# promini_3.net
KiCad netlist of a schematic drawn in EAGLE
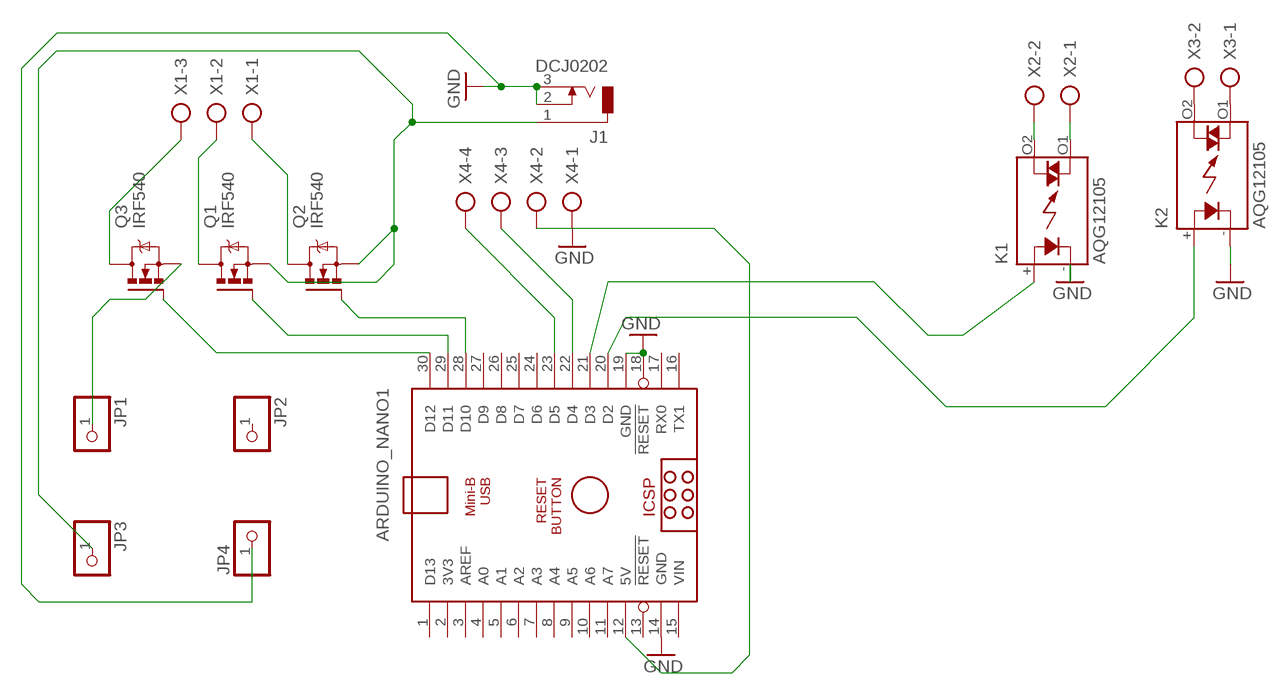
[diagram p0: schematic, sheet 1]

(export (version "E")
  (design (tool "Eeschema 10.0.6"))
  (components
    (comp (ref "ARDUINO_NANO1")
      (value "ARDUINO_NANO")
      (footprint "eagle-import:ARDUINO_NANO")
      (libsource (lib "eagle-import") (part "ARDUINO_NANO"))
    )
    (comp (ref "J1")
      (value "DCJ0202")
      (footprint "eagle-import:DCJ0202")
      (libsource (lib "eagle-import") (part "DCJ0202"))
    )
    (comp (ref "JP1")
      (value "PINHD-1X1")
      (footprint "eagle-import:1X01")
      (libsource (lib "eagle-import") (part "PINHD-1X1"))
    )
    (comp (ref "JP2")
      (value "PINHD-1X1")
      (footprint "eagle-import:1X01")
      (libsource (lib "eagle-import") (part "PINHD-1X1"))
    )
    (comp (ref "JP3")
      (value "PINHD-1X1")
      (footprint "eagle-import:1X01")
      (libsource (lib "eagle-import") (part "PINHD-1X1"))
    )
    (comp (ref "JP4")
      (value "PINHD-1X1")
      (footprint "eagle-import:1X01")
      (libsource (lib "eagle-import") (part "PINHD-1X1"))
    )
    (comp (ref "K1")
      (value "AQG12105")
      (footprint "eagle-import:AQG")
      (fields (field (name "MF") "AROMAT/ MATSUSHITA"))
      (libsource (lib "eagle-import") (part "AQG12105"))
    )
    (comp (ref "K2")
      (value "AQG12105")
      (footprint "eagle-import:AQG")
      (fields (field (name "MF") "AROMAT/ MATSUSHITA"))
      (libsource (lib "eagle-import") (part "AQG12105"))
    )
    (comp (ref "Q1")
      (value "IRF540")
      (footprint "eagle-import:TO220BV")
      (libsource (lib "eagle-import") (part "IRF540"))
    )
    (comp (ref "Q2")
      (value "IRF540")
      (footprint "eagle-import:TO220BV")
      (libsource (lib "eagle-import") (part "IRF540"))
    )
    (comp (ref "Q3")
      (value "IRF540")
      (footprint "eagle-import:TO220BV")
      (libsource (lib "eagle-import") (part "IRF540"))
    )
    (comp (ref "X1")
      (value "AK300/3")
      (footprint "eagle-import:AK300_3")
      (libsource (lib "eagle-import") (part "AK300/3"))
    )
    (comp (ref "X2")
      (value "AK300/2")
      (footprint "eagle-import:AK300_2")
      (libsource (lib "eagle-import") (part "AK300/2"))
    )
    (comp (ref "X3")
      (value "AK300/2")
      (footprint "eagle-import:AK300_2")
      (libsource (lib "eagle-import") (part "AK300/2"))
    )
    (comp (ref "X4")
      (value "AK300/4")
      (footprint "eagle-import:AK300_4")
      (libsource (lib "eagle-import") (part "AK300/4"))
    )
  )
  (nets
    (net (code "1") (name "/VIN") (class "Default")
      (node (ref "ARDUINO_NANO1") (pin "15") (pinfunction "VIN_15") (pintype "power_in"))
    )
    (net (code "2") (name "GND") (class "Default")
      (node (ref "ARDUINO_NANO1") (pin "14") (pinfunction "GND_14") (pintype "power_in"))
      (node (ref "ARDUINO_NANO1") (pin "18") (pinfunction "~{RESET}_18") (pintype "input"))
      (node (ref "ARDUINO_NANO1") (pin "19") (pinfunction "GND_19") (pintype "power_in"))
      (node (ref "J1") (pin "2") (pinfunction "2_2") (pintype "passive"))
      (node (ref "J1") (pin "3") (pinfunction "3_3") (pintype "passive"))
      (node (ref "JP4") (pin "1") (pinfunction "1_1") (pintype "passive"))
      (node (ref "K1") (pin "-") (pinfunction "K_-") (pintype "passive"))
      (node (ref "K2") (pin "-") (pinfunction "K_-") (pintype "passive"))
      (node (ref "X4") (pin "1") (pinfunction "KL_1") (pintype "passive"))
    )
    (net (code "3") (name "Net-(ARDUINO_NANO1-5V)") (class "Default")
      (node (ref "ARDUINO_NANO1") (pin "12") (pinfunction "5V_12") (pintype "power_in"))
      (node (ref "X4") (pin "2") (pinfunction "KL_2") (pintype "passive"))
    )
    (net (code "4") (name "Net-(ARDUINO_NANO1-D2)") (class "Default")
      (node (ref "ARDUINO_NANO1") (pin "20") (pinfunction "D2_20") (pintype "bidirectional"))
      (node (ref "K2") (pin "+") (pinfunction "A_+") (pintype "passive"))
    )
    (net (code "5") (name "Net-(ARDUINO_NANO1-D3)") (class "Default")
      (node (ref "ARDUINO_NANO1") (pin "21") (pinfunction "D3_21") (pintype "bidirectional"))
      (node (ref "K1") (pin "+") (pinfunction "A_+") (pintype "passive"))
    )
    (net (code "6") (name "Net-(ARDUINO_NANO1-D4)") (class "Default")
      (node (ref "ARDUINO_NANO1") (pin "22") (pinfunction "D4_22") (pintype "bidirectional"))
      (node (ref "X4") (pin "3") (pinfunction "KL_3") (pintype "passive"))
    )
    (net (code "7") (name "Net-(ARDUINO_NANO1-D5)") (class "Default")
      (node (ref "ARDUINO_NANO1") (pin "23") (pinfunction "D5_23") (pintype "bidirectional"))
      (node (ref "X4") (pin "4") (pinfunction "KL_4") (pintype "passive"))
    )
    (net (code "8") (name "Net-(ARDUINO_NANO1-D10)") (class "Default")
      (node (ref "ARDUINO_NANO1") (pin "28") (pinfunction "D10_28") (pintype "bidirectional"))
      (node (ref "Q2") (pin "G") (pinfunction "G_G") (pintype "passive"))
    )
    (net (code "9") (name "Net-(ARDUINO_NANO1-D11)") (class "Default")
      (node (ref "ARDUINO_NANO1") (pin "29") (pinfunction "D11_29") (pintype "bidirectional"))
      (node (ref "Q1") (pin "G") (pinfunction "G_G") (pintype "passive"))
    )
    (net (code "10") (name "Net-(ARDUINO_NANO1-D12)") (class "Default")
      (node (ref "ARDUINO_NANO1") (pin "30") (pinfunction "D12_30") (pintype "bidirectional"))
      (node (ref "Q3") (pin "G") (pinfunction "G_G") (pintype "passive"))
    )
    (net (code "11") (name "Net-(J1-Pad1)") (class "Default")
      (node (ref "J1") (pin "1") (pinfunction "1_1") (pintype "passive"))
      (node (ref "JP3") (pin "1") (pinfunction "1_1") (pintype "passive"))
      (node (ref "Q1") (pin "S") (pinfunction "S_S") (pintype "passive"))
      (node (ref "Q2") (pin "S") (pinfunction "S_S") (pintype "passive"))
    )
    (net (code "12") (name "Net-(JP1-Pad1)") (class "Default")
      (node (ref "JP1") (pin "1") (pinfunction "1_1") (pintype "passive"))
      (node (ref "Q3") (pin "S") (pinfunction "S_S") (pintype "passive"))
    )
    (net (code "13") (name "Net-(K1-DS1)") (class "Default")
      (node (ref "K1") (pin "O2") (pinfunction "DS1_O2") (pintype "passive"))
      (node (ref "X2") (pin "2") (pinfunction "KL_2") (pintype "passive"))
    )
    (net (code "14") (name "Net-(K1-DS2)") (class "Default")
      (node (ref "K1") (pin "O1") (pinfunction "DS2_O1") (pintype "passive"))
      (node (ref "X2") (pin "1") (pinfunction "KL_1") (pintype "passive"))
    )
    (net (code "15") (name "Net-(K2-DS1)") (class "Default")
      (node (ref "K2") (pin "O2") (pinfunction "DS1_O2") (pintype "passive"))
      (node (ref "X3") (pin "2") (pinfunction "KL_2") (pintype "passive"))
    )
    (net (code "16") (name "Net-(K2-DS2)") (class "Default")
      (node (ref "K2") (pin "O1") (pinfunction "DS2_O1") (pintype "passive"))
      (node (ref "X3") (pin "1") (pinfunction "KL_1") (pintype "passive"))
    )
    (net (code "17") (name "Net-(X1A-KL)") (class "Default")
      (node (ref "Q2") (pin "D") (pinfunction "D_D") (pintype "passive"))
      (node (ref "X1") (pin "1") (pinfunction "KL_1") (pintype "passive"))
    )
    (net (code "18") (name "Net-(X1B-KL)") (class "Default")
      (node (ref "Q1") (pin "D") (pinfunction "D_D") (pintype "passive"))
      (node (ref "X1") (pin "2") (pinfunction "KL_2") (pintype "passive"))
    )
    (net (code "19") (name "Net-(X1C-KL)") (class "Default")
      (node (ref "Q3") (pin "D") (pinfunction "D_D") (pintype "passive"))
      (node (ref "X1") (pin "3") (pinfunction "KL_3") (pintype "passive"))
    )
    (net (code "20") (name "unconnected-(ARDUINO_NANO1-3V3-Pad2)") (class "Default")
      (node (ref "ARDUINO_NANO1") (pin "2") (pinfunction "3V3_2") (pintype "output"))
    )
    (net (code "21") (name "unconnected-(ARDUINO_NANO1-A0-Pad4)") (class "Default")
      (node (ref "ARDUINO_NANO1") (pin "4") (pinfunction "A0_4") (pintype "bidirectional"))
    )
    (net (code "22") (name "unconnected-(ARDUINO_NANO1-A1-Pad5)") (class "Default")
      (node (ref "ARDUINO_NANO1") (pin "5") (pinfunction "A1_5") (pintype "bidirectional"))
    )
    (net (code "23") (name "unconnected-(ARDUINO_NANO1-A2-Pad6)") (class "Default")
      (node (ref "ARDUINO_NANO1") (pin "6") (pinfunction "A2_6") (pintype "bidirectional"))
    )
    (net (code "24") (name "unconnected-(ARDUINO_NANO1-A3-Pad7)") (class "Default")
      (node (ref "ARDUINO_NANO1") (pin "7") (pinfunction "A3_7") (pintype "bidirectional"))
    )
    (net (code "25") (name "unconnected-(ARDUINO_NANO1-A4-Pad8)") (class "Default")
      (node (ref "ARDUINO_NANO1") (pin "8") (pinfunction "A4_8") (pintype "bidirectional"))
    )
    (net (code "26") (name "unconnected-(ARDUINO_NANO1-A5-Pad9)") (class "Default")
      (node (ref "ARDUINO_NANO1") (pin "9") (pinfunction "A5_9") (pintype "bidirectional"))
    )
    (net (code "27") (name "unconnected-(ARDUINO_NANO1-A6-Pad10)") (class "Default")
      (node (ref "ARDUINO_NANO1") (pin "10") (pinfunction "A6_10") (pintype "bidirectional"))
    )
    (net (code "28") (name "unconnected-(ARDUINO_NANO1-A7-Pad11)") (class "Default")
      (node (ref "ARDUINO_NANO1") (pin "11") (pinfunction "A7_11") (pintype "bidirectional"))
    )
    (net (code "29") (name "unconnected-(ARDUINO_NANO1-AREF-Pad3)") (class "Default")
      (node (ref "ARDUINO_NANO1") (pin "3") (pinfunction "AREF_3") (pintype "input"))
    )
    (net (code "30") (name "unconnected-(ARDUINO_NANO1-D6-Pad24)") (class "Default")
      (node (ref "ARDUINO_NANO1") (pin "24") (pinfunction "D6_24") (pintype "bidirectional"))
    )
    (net (code "31") (name "unconnected-(ARDUINO_NANO1-D7-Pad25)") (class "Default")
      (node (ref "ARDUINO_NANO1") (pin "25") (pinfunction "D7_25") (pintype "bidirectional"))
    )
    (net (code "32") (name "unconnected-(ARDUINO_NANO1-D8-Pad26)") (class "Default")
      (node (ref "ARDUINO_NANO1") (pin "26") (pinfunction "D8_26") (pintype "bidirectional"))
    )
    (net (code "33") (name "unconnected-(ARDUINO_NANO1-D9-Pad27)") (class "Default")
      (node (ref "ARDUINO_NANO1") (pin "27") (pinfunction "D9_27") (pintype "bidirectional"))
    )
    (net (code "34") (name "unconnected-(ARDUINO_NANO1-D13-Pad1)") (class "Default")
      (node (ref "ARDUINO_NANO1") (pin "1") (pinfunction "D13_1") (pintype "bidirectional"))
    )
    (net (code "35") (name "unconnected-(ARDUINO_NANO1-RX0-Pad17)") (class "Default")
      (node (ref "ARDUINO_NANO1") (pin "17") (pinfunction "RX0_17") (pintype "bidirectional"))
    )
    (net (code "36") (name "unconnected-(ARDUINO_NANO1-TX1-Pad16)") (class "Default")
      (node (ref "ARDUINO_NANO1") (pin "16") (pinfunction "TX1_16") (pintype "bidirectional"))
    )
    (net (code "37") (name "unconnected-(ARDUINO_NANO1-~{RESET}-Pad13)") (class "Default")
      (node (ref "ARDUINO_NANO1") (pin "13") (pinfunction "~{RESET}_13") (pintype "input"))
    )
    (net (code "38") (name "unconnected-(JP2-Pad1)") (class "Default")
      (node (ref "JP2") (pin "1") (pinfunction "1_1") (pintype "passive"))
    )
  )
)
